# CANdiy-Shield_v21.net
KiCad netlist of a schematic drawn in EAGLE
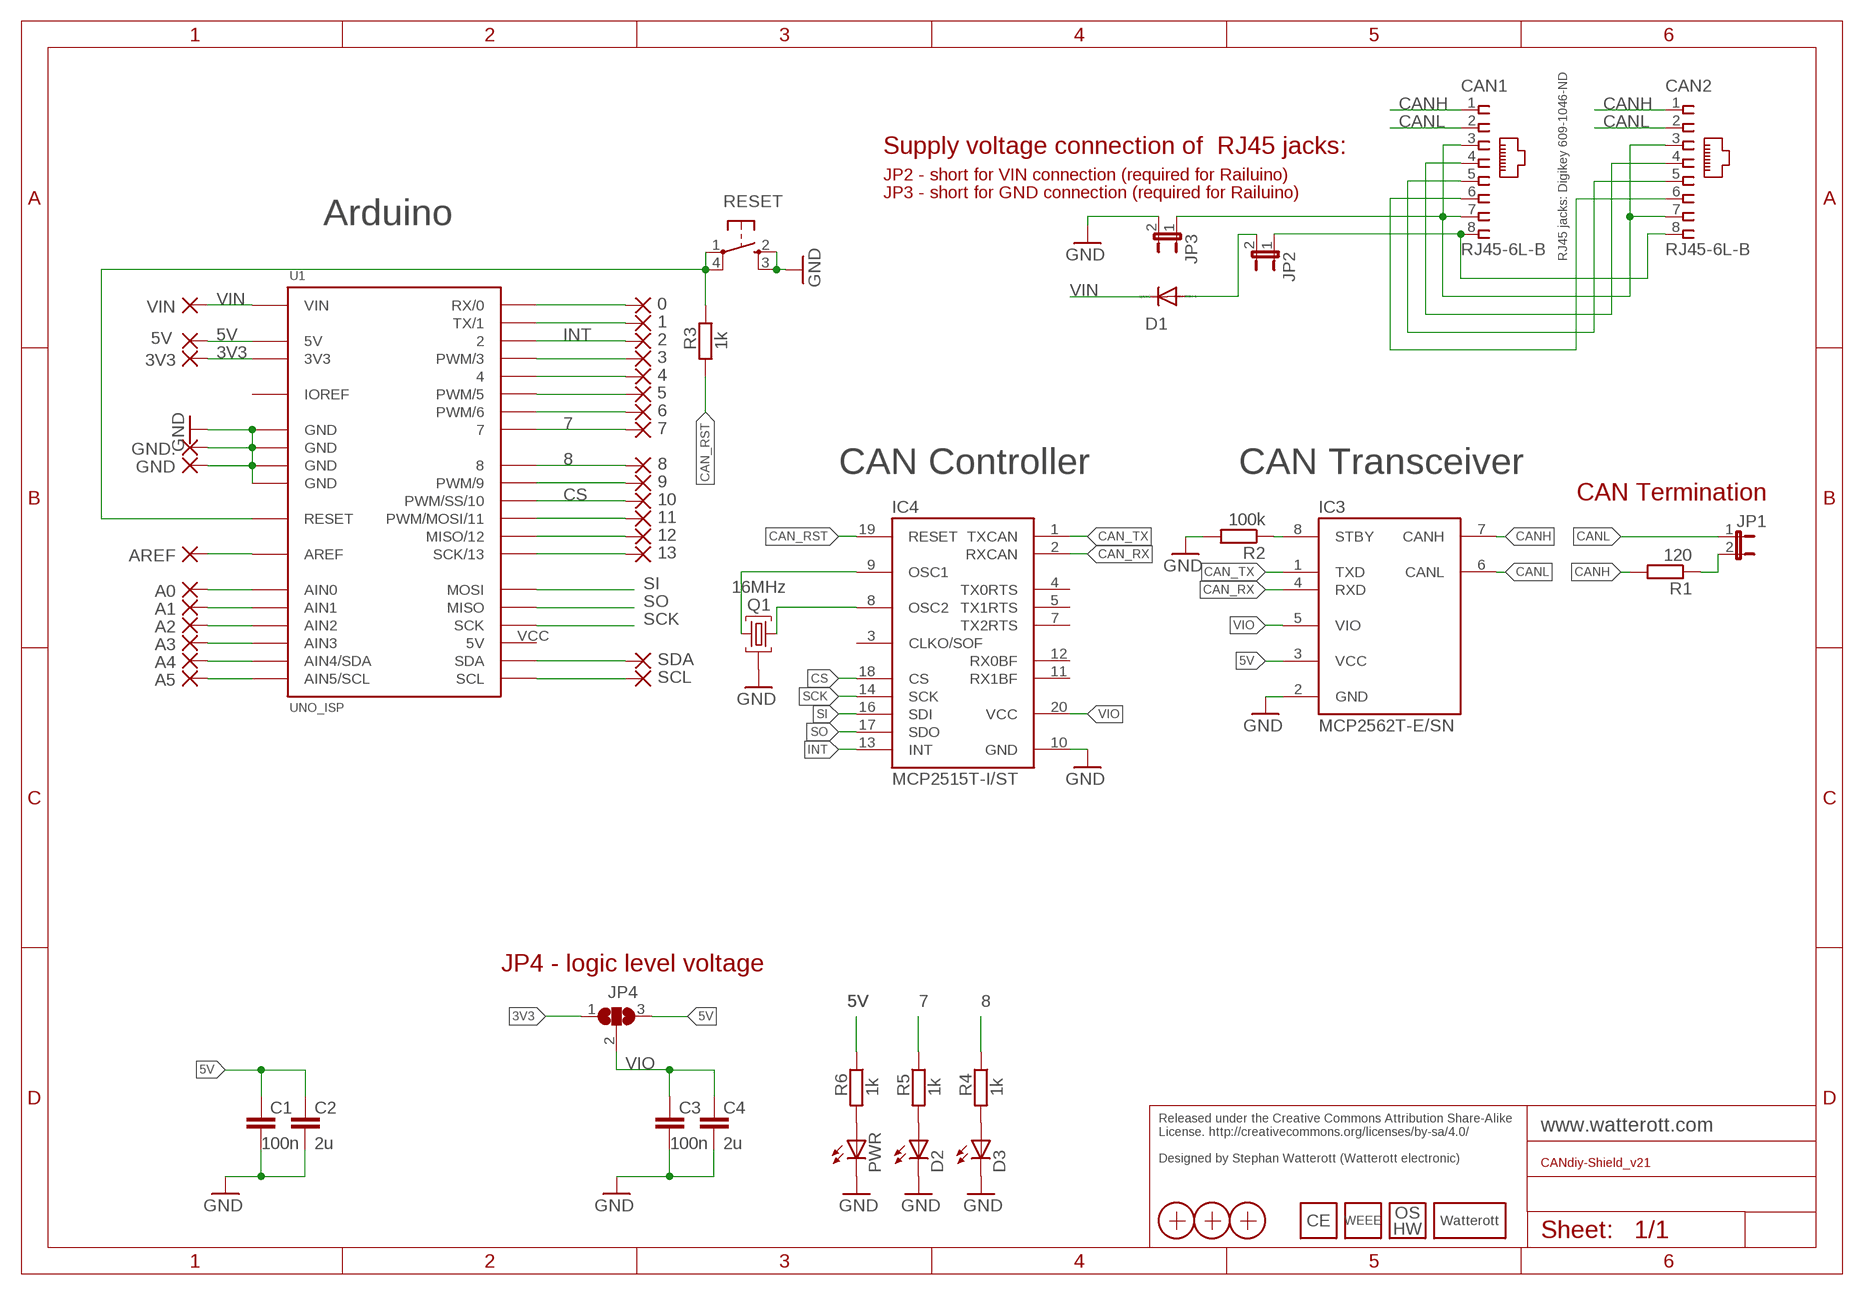
[diagram p0: schematic, sheet 1]

(export (version "E")
  (design (tool "Eeschema 10.0.6"))
  (components
    (comp (ref "0")
      (value "1,6/0,8")
      (footprint "eagle-import:1,6_0,8")
      (libsource (lib "eagle-import") (part "1,6/0,8"))
    )
    (comp (ref "1")
      (value "1,6/0,8")
      (footprint "eagle-import:1,6_0,8")
      (libsource (lib "eagle-import") (part "1,6/0,8"))
    )
    (comp (ref "2")
      (value "1,6/0,8")
      (footprint "eagle-import:1,6_0,8")
      (libsource (lib "eagle-import") (part "1,6/0,8"))
    )
    (comp (ref "3")
      (value "1,6/0,8")
      (footprint "eagle-import:1,6_0,8")
      (libsource (lib "eagle-import") (part "1,6/0,8"))
    )
    (comp (ref "3V3")
      (value "1,6/0,8")
      (footprint "eagle-import:1,6_0,8")
      (libsource (lib "eagle-import") (part "1,6/0,8"))
    )
    (comp (ref "4")
      (value "1,6/0,8")
      (footprint "eagle-import:1,6_0,8")
      (libsource (lib "eagle-import") (part "1,6/0,8"))
    )
    (comp (ref "5")
      (value "1,6/0,8")
      (footprint "eagle-import:1,6_0,8")
      (libsource (lib "eagle-import") (part "1,6/0,8"))
    )
    (comp (ref "5V")
      (value "1,6/0,8")
      (footprint "eagle-import:1,6_0,8")
      (libsource (lib "eagle-import") (part "1,6/0,8"))
    )
    (comp (ref "6")
      (value "1,6/0,8")
      (footprint "eagle-import:1,6_0,8")
      (libsource (lib "eagle-import") (part "1,6/0,8"))
    )
    (comp (ref "7")
      (value "1,6/0,8")
      (footprint "eagle-import:1,6_0,8")
      (libsource (lib "eagle-import") (part "1,6/0,8"))
    )
    (comp (ref "8")
      (value "1,6/0,8")
      (footprint "eagle-import:1,6_0,8")
      (libsource (lib "eagle-import") (part "1,6/0,8"))
    )
    (comp (ref "9")
      (value "1,6/0,8")
      (footprint "eagle-import:1,6_0,8")
      (libsource (lib "eagle-import") (part "1,6/0,8"))
    )
    (comp (ref "10")
      (value "1,6/0,8")
      (footprint "eagle-import:1,6_0,8")
      (libsource (lib "eagle-import") (part "1,6/0,8"))
    )
    (comp (ref "11")
      (value "1,6/0,8")
      (footprint "eagle-import:1,6_0,8")
      (libsource (lib "eagle-import") (part "1,6/0,8"))
    )
    (comp (ref "12")
      (value "1,6/0,8")
      (footprint "eagle-import:1,6_0,8")
      (libsource (lib "eagle-import") (part "1,6/0,8"))
    )
    (comp (ref "13")
      (value "1,6/0,8")
      (footprint "eagle-import:1,6_0,8")
      (libsource (lib "eagle-import") (part "1,6/0,8"))
    )
    (comp (ref "A0")
      (value "1,6/0,8")
      (footprint "eagle-import:1,6_0,8")
      (libsource (lib "eagle-import") (part "1,6/0,8"))
    )
    (comp (ref "A1")
      (value "1,6/0,8")
      (footprint "eagle-import:1,6_0,8")
      (libsource (lib "eagle-import") (part "1,6/0,8"))
    )
    (comp (ref "A2")
      (value "1,6/0,8")
      (footprint "eagle-import:1,6_0,8")
      (libsource (lib "eagle-import") (part "1,6/0,8"))
    )
    (comp (ref "A3")
      (value "1,6/0,8")
      (footprint "eagle-import:1,6_0,8")
      (libsource (lib "eagle-import") (part "1,6/0,8"))
    )
    (comp (ref "A4")
      (value "1,6/0,8")
      (footprint "eagle-import:1,6_0,8")
      (libsource (lib "eagle-import") (part "1,6/0,8"))
    )
    (comp (ref "A5")
      (value "1,6/0,8")
      (footprint "eagle-import:1,6_0,8")
      (libsource (lib "eagle-import") (part "1,6/0,8"))
    )
    (comp (ref "AREF")
      (value "1,6/0,8")
      (footprint "eagle-import:1,6_0,8")
      (libsource (lib "eagle-import") (part "1,6/0,8"))
    )
    (comp (ref "C1")
      (value "100n")
      (footprint "eagle-import:C0603")
      (libsource (lib "eagle-import") (part "C-EUC0603"))
    )
    (comp (ref "C2")
      (value "2u")
      (footprint "eagle-import:C0603")
      (libsource (lib "eagle-import") (part "C-EUC0603"))
    )
    (comp (ref "C3")
      (value "100n")
      (footprint "eagle-import:C0603")
      (libsource (lib "eagle-import") (part "C-EUC0603"))
    )
    (comp (ref "C4")
      (value "2u")
      (footprint "eagle-import:C0603")
      (libsource (lib "eagle-import") (part "C-EUC0603"))
    )
    (comp (ref "CAN1")
      (value "RJ45-6L-B")
      (footprint "eagle-import:RJ45-NO-SHIELD")
      (libsource (lib "eagle-import") (part "RJ45-6L-B"))
    )
    (comp (ref "CAN2")
      (value "RJ45-6L-B")
      (footprint "eagle-import:RJ45-NO-SHIELD")
      (libsource (lib "eagle-import") (part "RJ45-6L-B"))
    )
    (comp (ref "D1")
      (value "CGRM4001-G")
      (footprint "eagle-import:SOD-123_MINI-SMA")
      (libsource (lib "eagle-import") (part "CGRM400-G1"))
    )
    (comp (ref "D2")
      (value "LEDCHIPLED_0603")
      (footprint "eagle-import:CHIPLED_0603")
      (libsource (lib "eagle-import") (part "LEDCHIPLED_0603"))
    )
    (comp (ref "D3")
      (value "LEDCHIPLED_0603")
      (footprint "eagle-import:CHIPLED_0603")
      (libsource (lib "eagle-import") (part "LEDCHIPLED_0603"))
    )
    (comp (ref "GND")
      (value "1,6/0,8")
      (footprint "eagle-import:1,6_0,8")
      (libsource (lib "eagle-import") (part "1,6/0,8"))
    )
    (comp (ref "GND.")
      (value "1,6/0,8")
      (footprint "eagle-import:1,6_0,8")
      (libsource (lib "eagle-import") (part "1,6/0,8"))
    )
    (comp (ref "IC3")
      (value "MCP2562T-E/SN")
      (footprint "eagle-import:SO08")
      (libsource (lib "eagle-import") (part "MCP2562T-E/SN"))
    )
    (comp (ref "IC4")
      (value "MCP2515T-I/ST")
      (footprint "eagle-import:TSSOP20")
      (libsource (lib "eagle-import") (part "MCP2515T-I/ST"))
    )
    (comp (ref "JP1")
      (value "JP1E")
      (footprint "eagle-import:JP1")
      (libsource (lib "eagle-import") (part "JP1E"))
    )
    (comp (ref "JP2")
      (value "JP1E")
      (footprint "eagle-import:JP1")
      (libsource (lib "eagle-import") (part "JP1E"))
    )
    (comp (ref "JP3")
      (value "JP1E")
      (footprint "eagle-import:JP1")
      (libsource (lib "eagle-import") (part "JP1E"))
    )
    (comp (ref "JP4")
      (value "SJ2W")
      (footprint "eagle-import:SJ_2")
      (libsource (lib "eagle-import") (part "SJ2W"))
    )
    (comp (ref "LOGO3")
      (value "LOGO-9")
      (footprint "eagle-import:LOGO_9MM")
      (libsource (lib "eagle-import") (part "LOGO-9"))
    )
    (comp (ref "LOGO4")
      (value "LOGO_CE-2")
      (footprint "eagle-import:CE_2MM")
      (libsource (lib "eagle-import") (part "LOGO_CE-2"))
    )
    (comp (ref "LOGO5")
      (value "LOGO_OSHW-3")
      (footprint "eagle-import:OSHW_3MM")
      (libsource (lib "eagle-import") (part "LOGO_OSHW-3"))
    )
    (comp (ref "LOGO6")
      (value "LOGO_WEEE-4")
      (footprint "eagle-import:WEEE_4MM")
      (libsource (lib "eagle-import") (part "LOGO_WEEE-4"))
    )
    (comp (ref "PWR")
      (value "LEDCHIPLED_0603")
      (footprint "eagle-import:CHIPLED_0603")
      (libsource (lib "eagle-import") (part "LEDCHIPLED_0603"))
    )
    (comp (ref "Q1")
      (value "16MHz")
      (footprint "eagle-import:CRYSTAL_32X13")
      (libsource (lib "eagle-import") (part "CRYSTAL-RES-32"))
    )
    (comp (ref "R1")
      (value "120")
      (footprint "eagle-import:R0603")
      (libsource (lib "eagle-import") (part "resistor_R-EU_R0603"))
    )
    (comp (ref "R2")
      (value "100k")
      (footprint "eagle-import:R0603")
      (libsource (lib "eagle-import") (part "resistor_R-EU_R0603"))
    )
    (comp (ref "R3")
      (value "1k")
      (footprint "eagle-import:R0603")
      (libsource (lib "eagle-import") (part "R-EU_R0603"))
    )
    (comp (ref "R4")
      (value "1k")
      (footprint "eagle-import:R0603")
      (libsource (lib "eagle-import") (part "R-EU_R0603"))
    )
    (comp (ref "R5")
      (value "1k")
      (footprint "eagle-import:R0603")
      (libsource (lib "eagle-import") (part "R-EU_R0603"))
    )
    (comp (ref "R6")
      (value "1k")
      (footprint "eagle-import:R0603")
      (libsource (lib "eagle-import") (part "R-EU_R0603"))
    )
    (comp (ref "RESET")
      (value "SW_SMDS")
      (footprint "eagle-import:SW_SMD4")
      (libsource (lib "eagle-import") (part "SW_SMDS"))
    )
    (comp (ref "SCL")
      (value "1,6/0,8")
      (footprint "eagle-import:1,6_0,8")
      (libsource (lib "eagle-import") (part "1,6/0,8"))
    )
    (comp (ref "SDA")
      (value "1,6/0,8")
      (footprint "eagle-import:1,6_0,8")
      (libsource (lib "eagle-import") (part "1,6/0,8"))
    )
    (comp (ref "U1")
      (value "UNO_ISP")
      (footprint "eagle-import:UNO_ISP")
      (libsource (lib "eagle-import") (part "UNO_ISP"))
    )
    (comp (ref "VIN")
      (value "1,6/0,8")
      (footprint "eagle-import:1,6_0,8")
      (libsource (lib "eagle-import") (part "1,6/0,8"))
    )
    (comp (ref "X1")
      (value "PASSER-07")
      (footprint "eagle-import:PASSER_07MM")
      (libsource (lib "eagle-import") (part "PASSER-07"))
    )
    (comp (ref "X2")
      (value "PASSER-07")
      (footprint "eagle-import:PASSER_07MM")
      (libsource (lib "eagle-import") (part "PASSER-07"))
    )
    (comp (ref "X3")
      (value "PASSER-07")
      (footprint "eagle-import:PASSER_07MM")
      (libsource (lib "eagle-import") (part "PASSER-07"))
    )
  )
  (nets
    (net (code "1") (name "/7") (class "Default")
      (node (ref "7") (pin "1") (pinfunction "P_1") (pintype "passive"))
      (node (ref "R5") (pin "1") (pinfunction "1_1") (pintype "passive"))
      (node (ref "U1") (pin "7") (pinfunction "7_7") (pintype "bidirectional"))
    )
    (net (code "2") (name "/8") (class "Default")
      (node (ref "8") (pin "1") (pinfunction "P_1") (pintype "passive"))
      (node (ref "R4") (pin "1") (pinfunction "1_1") (pintype "passive"))
      (node (ref "U1") (pin "8") (pinfunction "8_8") (pintype "bidirectional"))
    )
    (net (code "3") (name "/IOREF") (class "Default")
      (node (ref "U1") (pin "IOREF") (pinfunction "IOREF_IOREF") (pintype "power_in"))
    )
    (net (code "4") (name "/VIN") (class "Default")
      (node (ref "D1") (pin "C") (pinfunction "C_C") (pintype "passive"))
      (node (ref "U1") (pin "VIN") (pinfunction "VIN_VIN") (pintype "power_in"))
      (node (ref "VIN") (pin "1") (pinfunction "P_1") (pintype "passive"))
    )
    (net (code "5") (name "3V3") (class "Default")
      (node (ref "3V3") (pin "1") (pinfunction "P_1") (pintype "passive"))
      (node (ref "JP4") (pin "1") (pinfunction "1_1") (pintype "passive"))
      (node (ref "U1") (pin "3V3") (pinfunction "3V3_3V3") (pintype "power_in"))
    )
    (net (code "6") (name "5V") (class "Default")
      (node (ref "5V") (pin "1") (pinfunction "P_1") (pintype "passive"))
      (node (ref "C1") (pin "1") (pinfunction "1_1") (pintype "passive"))
      (node (ref "C2") (pin "1") (pinfunction "1_1") (pintype "passive"))
      (node (ref "IC3") (pin "3") (pinfunction "VCC_3") (pintype "power_in"))
      (node (ref "JP4") (pin "3") (pinfunction "3_3") (pintype "passive"))
      (node (ref "R6") (pin "1") (pinfunction "1_1") (pintype "passive"))
      (node (ref "U1") (pin "5V") (pinfunction "5V_5V") (pintype "power_in"))
    )
    (net (code "7") (name "CANH") (class "Default")
      (node (ref "CAN1") (pin "1") (pinfunction "1_1") (pintype "passive"))
      (node (ref "CAN2") (pin "1") (pinfunction "1_1") (pintype "passive"))
      (node (ref "IC3") (pin "7") (pinfunction "CANH_7") (pintype "passive"))
      (node (ref "R1") (pin "2") (pinfunction "2_2") (pintype "passive"))
    )
    (net (code "8") (name "CANL") (class "Default")
      (node (ref "CAN1") (pin "2") (pinfunction "2_2") (pintype "passive"))
      (node (ref "CAN2") (pin "2") (pinfunction "2_2") (pintype "passive"))
      (node (ref "IC3") (pin "6") (pinfunction "CANL_6") (pintype "passive"))
      (node (ref "JP1") (pin "1") (pinfunction "1_1") (pintype "passive"))
    )
    (net (code "9") (name "CAN_RST") (class "Default")
      (node (ref "IC4") (pin "19") (pinfunction "RESET_19") (pintype "bidirectional"))
      (node (ref "R3") (pin "2") (pinfunction "2_2") (pintype "passive"))
    )
    (net (code "10") (name "CAN_RX") (class "Default")
      (node (ref "IC3") (pin "4") (pinfunction "RXD_4") (pintype "bidirectional"))
      (node (ref "IC4") (pin "2") (pinfunction "RXCAN_2") (pintype "bidirectional"))
    )
    (net (code "11") (name "CAN_TX") (class "Default")
      (node (ref "IC3") (pin "1") (pinfunction "TXD_1") (pintype "bidirectional"))
      (node (ref "IC4") (pin "1") (pinfunction "TXCAN_1") (pintype "bidirectional"))
    )
    (net (code "12") (name "CS") (class "Default")
      (node (ref "10") (pin "1") (pinfunction "P_1") (pintype "passive"))
      (node (ref "IC4") (pin "18") (pinfunction "CS_18") (pintype "bidirectional"))
      (node (ref "U1") (pin "10") (pinfunction "PWM/SS/10_10") (pintype "bidirectional"))
    )
    (net (code "13") (name "GND") (class "Default")
      (node (ref "C1") (pin "2") (pinfunction "2_2") (pintype "passive"))
      (node (ref "C2") (pin "2") (pinfunction "2_2") (pintype "passive"))
      (node (ref "C3") (pin "2") (pinfunction "2_2") (pintype "passive"))
      (node (ref "C4") (pin "2") (pinfunction "2_2") (pintype "passive"))
      (node (ref "D2") (pin "C") (pinfunction "C_C") (pintype "passive"))
      (node (ref "D3") (pin "C") (pinfunction "C_C") (pintype "passive"))
      (node (ref "GND") (pin "1") (pinfunction "P_1") (pintype "passive"))
      (node (ref "GND.") (pin "1") (pinfunction "P_1") (pintype "passive"))
      (node (ref "IC3") (pin "2") (pinfunction "GND_2") (pintype "power_in"))
      (node (ref "IC4") (pin "10") (pinfunction "GND_10") (pintype "power_in"))
      (node (ref "JP3") (pin "2") (pinfunction "2_2") (pintype "passive"))
      (node (ref "PWR") (pin "C") (pinfunction "C_C") (pintype "passive"))
      (node (ref "Q1") (pin "GND") (pinfunction "GND_GND") (pintype "passive"))
      (node (ref "R2") (pin "2") (pinfunction "2_2") (pintype "passive"))
      (node (ref "RESET") (pin "2") (pinfunction "S_2") (pintype "passive"))
      (node (ref "RESET") (pin "3") (pinfunction "S1_3") (pintype "passive"))
      (node (ref "U1") (pin "GND@1") (pinfunction "GND_GND@1") (pintype "power_in"))
      (node (ref "U1") (pin "GND@2") (pinfunction "GND_GND@2") (pintype "power_in"))
      (node (ref "U1") (pin "GND@3") (pinfunction "GND_GND@3") (pintype "power_in"))
      (node (ref "U1") (pin "GND@4") (pinfunction "GND_GND@4") (pintype "power_in"))
    )
    (net (code "14") (name "INT") (class "Default")
      (node (ref "2") (pin "1") (pinfunction "P_1") (pintype "passive"))
      (node (ref "IC4") (pin "13") (pinfunction "INT_13") (pintype "bidirectional"))
      (node (ref "U1") (pin "2") (pinfunction "2_2") (pintype "bidirectional"))
    )
    (net (code "15") (name "Net-(0-P)") (class "Default")
      (node (ref "0") (pin "1") (pinfunction "P_1") (pintype "passive"))
      (node (ref "U1") (pin "0") (pinfunction "RX/0_0") (pintype "bidirectional"))
    )
    (net (code "16") (name "Net-(1-P)") (class "Default")
      (node (ref "1") (pin "1") (pinfunction "P_1") (pintype "passive"))
      (node (ref "U1") (pin "1") (pinfunction "TX/1_1") (pintype "bidirectional"))
    )
    (net (code "17") (name "Net-(3-P)") (class "Default")
      (node (ref "3") (pin "1") (pinfunction "P_1") (pintype "passive"))
      (node (ref "U1") (pin "3") (pinfunction "PWM/3_3") (pintype "bidirectional"))
    )
    (net (code "18") (name "Net-(4-P)") (class "Default")
      (node (ref "4") (pin "1") (pinfunction "P_1") (pintype "passive"))
      (node (ref "U1") (pin "4") (pinfunction "4_4") (pintype "bidirectional"))
    )
    (net (code "19") (name "Net-(5-P)") (class "Default")
      (node (ref "5") (pin "1") (pinfunction "P_1") (pintype "passive"))
      (node (ref "U1") (pin "5") (pinfunction "PWM/5_5") (pintype "bidirectional"))
    )
    (net (code "20") (name "Net-(6-P)") (class "Default")
      (node (ref "6") (pin "1") (pinfunction "P_1") (pintype "passive"))
      (node (ref "U1") (pin "6") (pinfunction "PWM/6_6") (pintype "bidirectional"))
    )
    (net (code "21") (name "Net-(9-P)") (class "Default")
      (node (ref "9") (pin "1") (pinfunction "P_1") (pintype "passive"))
      (node (ref "U1") (pin "9") (pinfunction "PWM/9_9") (pintype "bidirectional"))
    )
    (net (code "22") (name "Net-(11-P)") (class "Default")
      (node (ref "11") (pin "1") (pinfunction "P_1") (pintype "passive"))
      (node (ref "U1") (pin "11") (pinfunction "PWM/MOSI/11_11") (pintype "bidirectional"))
    )
    (net (code "23") (name "Net-(12-P)") (class "Default")
      (node (ref "12") (pin "1") (pinfunction "P_1") (pintype "passive"))
      (node (ref "U1") (pin "12") (pinfunction "MISO/12_12") (pintype "bidirectional"))
    )
    (net (code "24") (name "Net-(13-P)") (class "Default")
      (node (ref "13") (pin "1") (pinfunction "P_1") (pintype "passive"))
      (node (ref "U1") (pin "13") (pinfunction "SCK/13_13") (pintype "bidirectional"))
    )
    (net (code "25") (name "Net-(A0-P)") (class "Default")
      (node (ref "A0") (pin "1") (pinfunction "P_1") (pintype "passive"))
      (node (ref "U1") (pin "AIN0") (pinfunction "AIN0_AIN0") (pintype "bidirectional"))
    )
    (net (code "26") (name "Net-(A1-P)") (class "Default")
      (node (ref "A1") (pin "1") (pinfunction "P_1") (pintype "passive"))
      (node (ref "U1") (pin "AIN1") (pinfunction "AIN1_AIN1") (pintype "bidirectional"))
    )
    (net (code "27") (name "Net-(A2-P)") (class "Default")
      (node (ref "A2") (pin "1") (pinfunction "P_1") (pintype "passive"))
      (node (ref "U1") (pin "AIN2") (pinfunction "AIN2_AIN2") (pintype "bidirectional"))
    )
    (net (code "28") (name "Net-(A3-P)") (class "Default")
      (node (ref "A3") (pin "1") (pinfunction "P_1") (pintype "passive"))
      (node (ref "U1") (pin "AIN3") (pinfunction "AIN3_AIN3") (pintype "bidirectional"))
    )
    (net (code "29") (name "Net-(A4-P)") (class "Default")
      (node (ref "A4") (pin "1") (pinfunction "P_1") (pintype "passive"))
      (node (ref "U1") (pin "AIN4") (pinfunction "AIN4/SDA_AIN4") (pintype "bidirectional"))
    )
    (net (code "30") (name "Net-(A5-P)") (class "Default")
      (node (ref "A5") (pin "1") (pinfunction "P_1") (pintype "passive"))
      (node (ref "U1") (pin "AIN5") (pinfunction "AIN5/SCL_AIN5") (pintype "bidirectional"))
    )
    (net (code "31") (name "Net-(AREF-P)") (class "Default")
      (node (ref "AREF") (pin "1") (pinfunction "P_1") (pintype "passive"))
      (node (ref "U1") (pin "AREF") (pinfunction "AREF_AREF") (pintype "power_in"))
    )
    (net (code "32") (name "Net-(CAN1-Pad3)") (class "Default")
      (node (ref "CAN1") (pin "3") (pinfunction "3_3") (pintype "passive"))
      (node (ref "CAN1") (pin "7") (pinfunction "7_7") (pintype "passive"))
      (node (ref "CAN2") (pin "3") (pinfunction "3_3") (pintype "passive"))
      (node (ref "CAN2") (pin "7") (pinfunction "7_7") (pintype "passive"))
      (node (ref "JP3") (pin "1") (pinfunction "1_1") (pintype "passive"))
    )
    (net (code "33") (name "Net-(CAN1-Pad4)") (class "Default")
      (node (ref "CAN1") (pin "4") (pinfunction "4_4") (pintype "passive"))
      (node (ref "CAN2") (pin "4") (pinfunction "4_4") (pintype "passive"))
    )
    (net (code "34") (name "Net-(CAN1-Pad5)") (class "Default")
      (node (ref "CAN1") (pin "5") (pinfunction "5_5") (pintype "passive"))
      (node (ref "CAN2") (pin "5") (pinfunction "5_5") (pintype "passive"))
    )
    (net (code "35") (name "Net-(CAN1-Pad6)") (class "Default")
      (node (ref "CAN1") (pin "6") (pinfunction "6_6") (pintype "passive"))
      (node (ref "CAN2") (pin "6") (pinfunction "6_6") (pintype "passive"))
    )
    (net (code "36") (name "Net-(CAN1-Pad8)") (class "Default")
      (node (ref "CAN1") (pin "8") (pinfunction "8_8") (pintype "passive"))
      (node (ref "CAN2") (pin "8") (pinfunction "8_8") (pintype "passive"))
      (node (ref "JP2") (pin "1") (pinfunction "1_1") (pintype "passive"))
    )
    (net (code "37") (name "Net-(D1-PadA)") (class "Default")
      (node (ref "D1") (pin "A") (pinfunction "A_A") (pintype "passive"))
      (node (ref "JP2") (pin "2") (pinfunction "2_2") (pintype "passive"))
    )
    (net (code "38") (name "Net-(D2-PadA)") (class "Default")
      (node (ref "D2") (pin "A") (pinfunction "A_A") (pintype "passive"))
      (node (ref "R5") (pin "2") (pinfunction "2_2") (pintype "passive"))
    )
    (net (code "39") (name "Net-(D3-PadA)") (class "Default")
      (node (ref "D3") (pin "A") (pinfunction "A_A") (pintype "passive"))
      (node (ref "R4") (pin "2") (pinfunction "2_2") (pintype "passive"))
    )
    (net (code "40") (name "Net-(IC3-STBY)") (class "Default")
      (node (ref "IC3") (pin "8") (pinfunction "STBY_8") (pintype "bidirectional"))
      (node (ref "R2") (pin "1") (pinfunction "1_1") (pintype "passive"))
    )
    (net (code "41") (name "Net-(IC4-OSC1)") (class "Default")
      (node (ref "IC4") (pin "9") (pinfunction "OSC1_9") (pintype "bidirectional"))
      (node (ref "Q1") (pin "2") (pinfunction "2_2") (pintype "passive"))
    )
    (net (code "42") (name "Net-(IC4-OSC2)") (class "Default")
      (node (ref "IC4") (pin "8") (pinfunction "OSC2_8") (pintype "bidirectional"))
      (node (ref "Q1") (pin "1") (pinfunction "1_1") (pintype "passive"))
    )
    (net (code "43") (name "Net-(JP1-Pad2)") (class "Default")
      (node (ref "JP1") (pin "2") (pinfunction "2_2") (pintype "passive"))
      (node (ref "R1") (pin "1") (pinfunction "1_1") (pintype "passive"))
    )
    (net (code "44") (name "Net-(PWR-PadA)") (class "Default")
      (node (ref "PWR") (pin "A") (pinfunction "A_A") (pintype "passive"))
      (node (ref "R6") (pin "2") (pinfunction "2_2") (pintype "passive"))
    )
    (net (code "45") (name "Net-(RESET-P)") (class "Default")
      (node (ref "R3") (pin "1") (pinfunction "1_1") (pintype "passive"))
      (node (ref "RESET") (pin "1") (pinfunction "P_1") (pintype "passive"))
      (node (ref "RESET") (pin "4") (pinfunction "P1_4") (pintype "passive"))
      (node (ref "U1") (pin "RST") (pinfunction "RESET_RST") (pintype "bidirectional"))
    )
    (net (code "46") (name "Net-(SCL-P)") (class "Default")
      (node (ref "SCL") (pin "1") (pinfunction "P_1") (pintype "passive"))
      (node (ref "U1") (pin "SCL") (pinfunction "SCL_SCL") (pintype "bidirectional"))
    )
    (net (code "47") (name "Net-(SDA-P)") (class "Default")
      (node (ref "SDA") (pin "1") (pinfunction "P_1") (pintype "passive"))
      (node (ref "U1") (pin "SDA") (pinfunction "SDA_SDA") (pintype "bidirectional"))
    )
    (net (code "48") (name "SCK") (class "Default")
      (node (ref "IC4") (pin "14") (pinfunction "SCK_14") (pintype "bidirectional"))
      (node (ref "U1") (pin "SCK") (pinfunction "SCK_SCK") (pintype "bidirectional"))
    )
    (net (code "49") (name "SI") (class "Default")
      (node (ref "IC4") (pin "16") (pinfunction "SDI_16") (pintype "bidirectional"))
      (node (ref "U1") (pin "MOSI") (pinfunction "MOSI_MOSI") (pintype "bidirectional"))
    )
    (net (code "50") (name "SO") (class "Default")
      (node (ref "IC4") (pin "17") (pinfunction "SDO_17") (pintype "bidirectional"))
      (node (ref "U1") (pin "MISO") (pinfunction "MISO_MISO") (pintype "bidirectional"))
    )
    (net (code "51") (name "VIO") (class "Default")
      (node (ref "C3") (pin "1") (pinfunction "1_1") (pintype "passive"))
      (node (ref "C4") (pin "1") (pinfunction "1_1") (pintype "passive"))
      (node (ref "IC3") (pin "5") (pinfunction "VIO_5") (pintype "power_in"))
      (node (ref "IC4") (pin "20") (pinfunction "VCC_20") (pintype "power_in"))
      (node (ref "JP4") (pin "2") (pinfunction "2_2") (pintype "passive"))
    )
    (net (code "52") (name "unconnected-(IC4-CLKO{slash}SOF-Pad3)") (class "Default")
      (node (ref "IC4") (pin "3") (pinfunction "CLKO/SOF_3") (pintype "bidirectional"))
    )
    (net (code "53") (name "unconnected-(IC4-RX0BF-Pad12)") (class "Default")
      (node (ref "IC4") (pin "12") (pinfunction "RX0BF_12") (pintype "bidirectional"))
    )
    (net (code "54") (name "unconnected-(IC4-RX1BF-Pad11)") (class "Default")
      (node (ref "IC4") (pin "11") (pinfunction "RX1BF_11") (pintype "bidirectional"))
    )
    (net (code "55") (name "unconnected-(IC4-TX0RTS-Pad4)") (class "Default")
      (node (ref "IC4") (pin "4") (pinfunction "TX0RTS_4") (pintype "bidirectional"))
    )
    (net (code "56") (name "unconnected-(IC4-TX1RTS-Pad5)") (class "Default")
      (node (ref "IC4") (pin "5") (pinfunction "TX1RTS_5") (pintype "bidirectional"))
    )
    (net (code "57") (name "unconnected-(IC4-TX2RTS-Pad7)") (class "Default")
      (node (ref "IC4") (pin "7") (pinfunction "TX2RTS_7") (pintype "bidirectional"))
    )
    (net (code "58") (name "unconnected-(U1-5V-PadVCC)") (class "Default")
      (node (ref "U1") (pin "VCC") (pinfunction "5V_VCC") (pintype "bidirectional"))
    )
  )
)
